# NTC_Head.net
KiCad netlist of a schematic drawn in Altium Designer
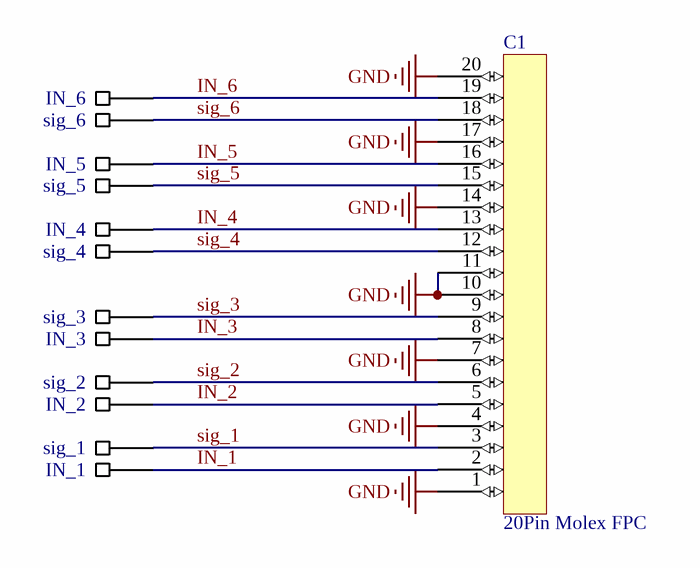
[diagram p0: NTC_Head.SchDoc]

(export (version "E")
  (design (tool "Eeschema 10.0.6"))
  (components
    (comp (ref "C1")
      (value "20Pin Molex FPC")
      (footprint "Molex 20 Pin FPC")
      (description "Flex PCB part for the Molex 20pin FCC")
      (libsource (lib "Integrated_LibraryLukas_New") (part "20Pin Molex FPC"))
    )
    (comp (ref "IN_1")
      (value "Pad")
      (footprint "Generic_Pad_1.5x1.5")
      (description "Pad 1.5mm x 1.5mm")
      (libsource (lib "libNico") (part "Generic_Pad_1.5x1.5"))
    )
    (comp (ref "IN_2")
      (value "Pad")
      (footprint "Generic_Pad_1.5x1.5")
      (description "Pad 1.5mm x 1.5mm")
      (libsource (lib "libNico") (part "Generic_Pad_1.5x1.5"))
    )
    (comp (ref "IN_3")
      (value "Pad")
      (footprint "Generic_Pad_1.5x1.5")
      (description "Pad 1.5mm x 1.5mm")
      (libsource (lib "libNico") (part "Generic_Pad_1.5x1.5"))
    )
    (comp (ref "IN_4")
      (value "Pad")
      (footprint "Generic_Pad_1.5x1.5")
      (description "Pad 1.5mm x 1.5mm")
      (libsource (lib "libNico") (part "Generic_Pad_1.5x1.5"))
    )
    (comp (ref "IN_5")
      (value "Pad")
      (footprint "Generic_Pad_1.5x1.5")
      (description "Pad 1.5mm x 1.5mm")
      (libsource (lib "libNico") (part "Generic_Pad_1.5x1.5"))
    )
    (comp (ref "IN_6")
      (value "Pad")
      (footprint "Generic_Pad_1.5x1.5")
      (description "Pad 1.5mm x 1.5mm")
      (libsource (lib "libNico") (part "Generic_Pad_1.5x1.5"))
    )
    (comp (ref "sig_1")
      (value "Pad")
      (footprint "Generic_Pad_1.5x1.5")
      (description "Pad 1.5mm x 1.5mm")
      (libsource (lib "libNico") (part "Generic_Pad_1.5x1.5"))
    )
    (comp (ref "sig_2")
      (value "Pad")
      (footprint "Generic_Pad_1.5x1.5")
      (description "Pad 1.5mm x 1.5mm")
      (libsource (lib "libNico") (part "Generic_Pad_1.5x1.5"))
    )
    (comp (ref "sig_3")
      (value "Pad")
      (footprint "Generic_Pad_1.5x1.5")
      (description "Pad 1.5mm x 1.5mm")
      (libsource (lib "libNico") (part "Generic_Pad_1.5x1.5"))
    )
    (comp (ref "sig_4")
      (value "Pad")
      (footprint "Generic_Pad_1.5x1.5")
      (description "Pad 1.5mm x 1.5mm")
      (libsource (lib "libNico") (part "Generic_Pad_1.5x1.5"))
    )
    (comp (ref "sig_5")
      (value "Pad")
      (footprint "Generic_Pad_1.5x1.5")
      (description "Pad 1.5mm x 1.5mm")
      (libsource (lib "libNico") (part "Generic_Pad_1.5x1.5"))
    )
    (comp (ref "sig_6")
      (value "Pad")
      (footprint "Generic_Pad_1.5x1.5")
      (description "Pad 1.5mm x 1.5mm")
      (libsource (lib "libNico") (part "Generic_Pad_1.5x1.5"))
    )
  )
  (nets
    (net (code "1") (name "/IN_1") (class "Default")
      (node (ref "C1") (pin "2") (pintype "bidirectional"))
      (node (ref "IN_1") (pin "P") (pinfunction "Pad_P") (pintype "passive"))
    )
    (net (code "2") (name "/IN_2") (class "Default")
      (node (ref "C1") (pin "5") (pintype "bidirectional"))
      (node (ref "IN_2") (pin "P") (pinfunction "Pad_P") (pintype "passive"))
    )
    (net (code "3") (name "/IN_3") (class "Default")
      (node (ref "C1") (pin "8") (pintype "bidirectional"))
      (node (ref "IN_3") (pin "P") (pinfunction "Pad_P") (pintype "passive"))
    )
    (net (code "4") (name "/IN_4") (class "Default")
      (node (ref "C1") (pin "13") (pintype "bidirectional"))
      (node (ref "IN_4") (pin "P") (pinfunction "Pad_P") (pintype "passive"))
    )
    (net (code "5") (name "/IN_5") (class "Default")
      (node (ref "C1") (pin "16") (pintype "bidirectional"))
      (node (ref "IN_5") (pin "P") (pinfunction "Pad_P") (pintype "passive"))
    )
    (net (code "6") (name "/IN_6") (class "Default")
      (node (ref "C1") (pin "19") (pintype "bidirectional"))
      (node (ref "IN_6") (pin "P") (pinfunction "Pad_P") (pintype "passive"))
    )
    (net (code "7") (name "/sig_1") (class "Default")
      (node (ref "C1") (pin "3") (pintype "bidirectional"))
      (node (ref "sig_1") (pin "P") (pinfunction "Pad_P") (pintype "passive"))
    )
    (net (code "8") (name "/sig_2") (class "Default")
      (node (ref "C1") (pin "6") (pintype "bidirectional"))
      (node (ref "sig_2") (pin "P") (pinfunction "Pad_P") (pintype "passive"))
    )
    (net (code "9") (name "/sig_3") (class "Default")
      (node (ref "C1") (pin "9") (pintype "bidirectional"))
      (node (ref "sig_3") (pin "P") (pinfunction "Pad_P") (pintype "passive"))
    )
    (net (code "10") (name "/sig_4") (class "Default")
      (node (ref "C1") (pin "12") (pintype "bidirectional"))
      (node (ref "sig_4") (pin "P") (pinfunction "Pad_P") (pintype "passive"))
    )
    (net (code "11") (name "/sig_5") (class "Default")
      (node (ref "C1") (pin "15") (pintype "bidirectional"))
      (node (ref "sig_5") (pin "P") (pinfunction "Pad_P") (pintype "passive"))
    )
    (net (code "12") (name "/sig_6") (class "Default")
      (node (ref "C1") (pin "18") (pintype "bidirectional"))
      (node (ref "sig_6") (pin "P") (pinfunction "Pad_P") (pintype "passive"))
    )
    (net (code "13") (name "GND") (class "Default")
      (node (ref "C1") (pin "1") (pintype "bidirectional"))
      (node (ref "C1") (pin "10") (pintype "bidirectional"))
      (node (ref "C1") (pin "11") (pintype "bidirectional"))
      (node (ref "C1") (pin "14") (pintype "bidirectional"))
      (node (ref "C1") (pin "17") (pintype "bidirectional"))
      (node (ref "C1") (pin "20") (pintype "bidirectional"))
      (node (ref "C1") (pin "4") (pintype "bidirectional"))
      (node (ref "C1") (pin "7") (pintype "bidirectional"))
    )
  )
)
